# YLT1.net
KiCad netlist of a schematic drawn in Altium Designer
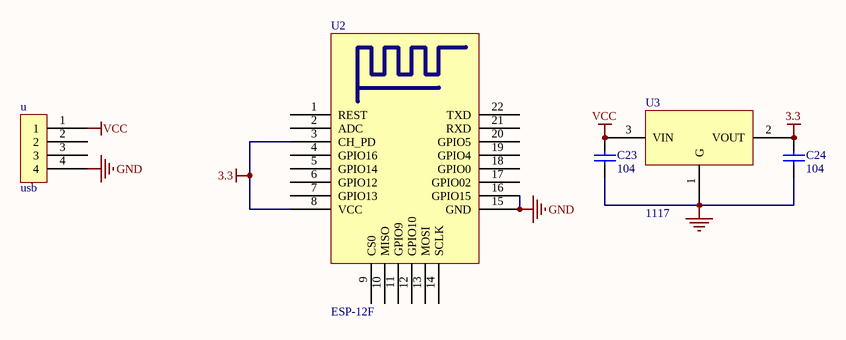
[diagram p0: YLT1.SchDoc]

(export (version "E")
  (design (tool "Eeschema 10.0.6"))
  (components
    (comp (ref "C23")
      (value "104")
      (footprint "0603C")
      (description "Capacitor")
      (fields (field (name "Comment") "Cap") (field (name "PUBLISHER") "Altium Limited"))
      (libsource (lib "Miscellaneous Devices") (part "Cap"))
    )
    (comp (ref "C24")
      (value "104")
      (footprint "0603C")
      (description "Capacitor")
      (fields (field (name "Comment") "Cap") (field (name "PUBLISHER") "Altium Limited"))
      (libsource (lib "Miscellaneous Devices") (part "Cap"))
    )
    (comp (ref "u") (value "usb") (footprint "PCBComponent_1") (libsource (lib "WIFI") (part "usb")))
    (comp (ref "U2") (value "ESP-12F") (footprint "LCC22_wifi") (libsource (lib "WIFI") (part "ESP-12F")))
    (comp (ref "U3") (value "1117") (footprint "SOT223") (libsource (lib "原理图封装库") (part "117")))
  )
  (nets
    (net (code "1") (name "3.3") (class "Default")
      (node (ref "C24") (pin "2") (pinfunction "2_2") (pintype "passive"))
      (node (ref "U2") (pin "3") (pinfunction "CH_PD_3") (pintype "passive"))
      (node (ref "U2") (pin "8") (pinfunction "VCC_8") (pintype "passive"))
      (node (ref "U3") (pin "2") (pinfunction "VOUT_2") (pintype "passive"))
    )
    (net (code "2") (name "GND") (class "Default")
      (node (ref "C23") (pin "1") (pinfunction "1_1") (pintype "passive"))
      (node (ref "C24") (pin "1") (pinfunction "1_1") (pintype "passive"))
      (node (ref "U2") (pin "15") (pinfunction "GND_15") (pintype "passive"))
      (node (ref "U2") (pin "16") (pinfunction "GPIO15_16") (pintype "passive"))
      (node (ref "U3") (pin "1") (pinfunction "G_1") (pintype "passive"))
      (node (ref "u") (pin "4") (pinfunction "4_4") (pintype "passive"))
    )
    (net (code "3") (name "VCC") (class "Default")
      (node (ref "C23") (pin "2") (pinfunction "2_2") (pintype "passive"))
      (node (ref "U3") (pin "3") (pinfunction "VIN_3") (pintype "passive"))
      (node (ref "u") (pin "1") (pinfunction "1_1") (pintype "passive"))
    )
    (net (code "4") (name "unconnected-(U2-ADC-Pad2)") (class "Default")
      (node (ref "U2") (pin "2") (pinfunction "ADC_2") (pintype "passive"))
    )
    (net (code "5") (name "unconnected-(U2-CS0-Pad9)") (class "Default")
      (node (ref "U2") (pin "9") (pinfunction "CS0_9") (pintype "passive"))
    )
    (net (code "6") (name "unconnected-(U2-GPIO0-Pad18)") (class "Default")
      (node (ref "U2") (pin "18") (pinfunction "GPIO0_18") (pintype "passive"))
    )
    (net (code "7") (name "unconnected-(U2-GPIO02-Pad17)") (class "Default")
      (node (ref "U2") (pin "17") (pinfunction "GPIO02_17") (pintype "passive"))
    )
    (net (code "8") (name "unconnected-(U2-GPIO4-Pad19)") (class "Default")
      (node (ref "U2") (pin "19") (pinfunction "GPIO4_19") (pintype "passive"))
    )
    (net (code "9") (name "unconnected-(U2-GPIO5-Pad20)") (class "Default")
      (node (ref "U2") (pin "20") (pinfunction "GPIO5_20") (pintype "passive"))
    )
    (net (code "10") (name "unconnected-(U2-GPIO9-Pad11)") (class "Default")
      (node (ref "U2") (pin "11") (pinfunction "GPIO9_11") (pintype "passive"))
    )
    (net (code "11") (name "unconnected-(U2-GPIO10-Pad12)") (class "Default")
      (node (ref "U2") (pin "12") (pinfunction "GPIO10_12") (pintype "passive"))
    )
    (net (code "12") (name "unconnected-(U2-GPIO12-Pad6)") (class "Default")
      (node (ref "U2") (pin "6") (pinfunction "GPIO12_6") (pintype "passive"))
    )
    (net (code "13") (name "unconnected-(U2-GPIO13-Pad7)") (class "Default")
      (node (ref "U2") (pin "7") (pinfunction "GPIO13_7") (pintype "passive"))
    )
    (net (code "14") (name "unconnected-(U2-GPIO14-Pad5)") (class "Default")
      (node (ref "U2") (pin "5") (pinfunction "GPIO14_5") (pintype "passive"))
    )
    (net (code "15") (name "unconnected-(U2-GPIO16-Pad4)") (class "Default")
      (node (ref "U2") (pin "4") (pinfunction "GPIO16_4") (pintype "passive"))
    )
    (net (code "16") (name "unconnected-(U2-MISO-Pad10)") (class "Default")
      (node (ref "U2") (pin "10") (pinfunction "MISO_10") (pintype "passive"))
    )
    (net (code "17") (name "unconnected-(U2-MOSI-Pad13)") (class "Default")
      (node (ref "U2") (pin "13") (pinfunction "MOSI_13") (pintype "passive"))
    )
    (net (code "18") (name "unconnected-(U2-REST-Pad1)") (class "Default")
      (node (ref "U2") (pin "1") (pinfunction "REST_1") (pintype "passive"))
    )
    (net (code "19") (name "unconnected-(U2-RXD-Pad21)") (class "Default")
      (node (ref "U2") (pin "21") (pinfunction "RXD_21") (pintype "passive"))
    )
    (net (code "20") (name "unconnected-(U2-SCLK-Pad14)") (class "Default")
      (node (ref "U2") (pin "14") (pinfunction "SCLK_14") (pintype "passive"))
    )
    (net (code "21") (name "unconnected-(U2-TXD-Pad22)") (class "Default")
      (node (ref "U2") (pin "22") (pinfunction "TXD_22") (pintype "passive"))
    )
    (net (code "22") (name "unconnected-(u-Pad2)") (class "Default")
      (node (ref "u") (pin "2") (pinfunction "2_2") (pintype "passive"))
    )
    (net (code "23") (name "unconnected-(u-Pad3)") (class "Default")
      (node (ref "u") (pin "3") (pinfunction "3_3") (pintype "passive"))
    )
  )
)
